# Volterra_Doughter_Board.net
KiCad netlist of a schematic drawn in EAGLE
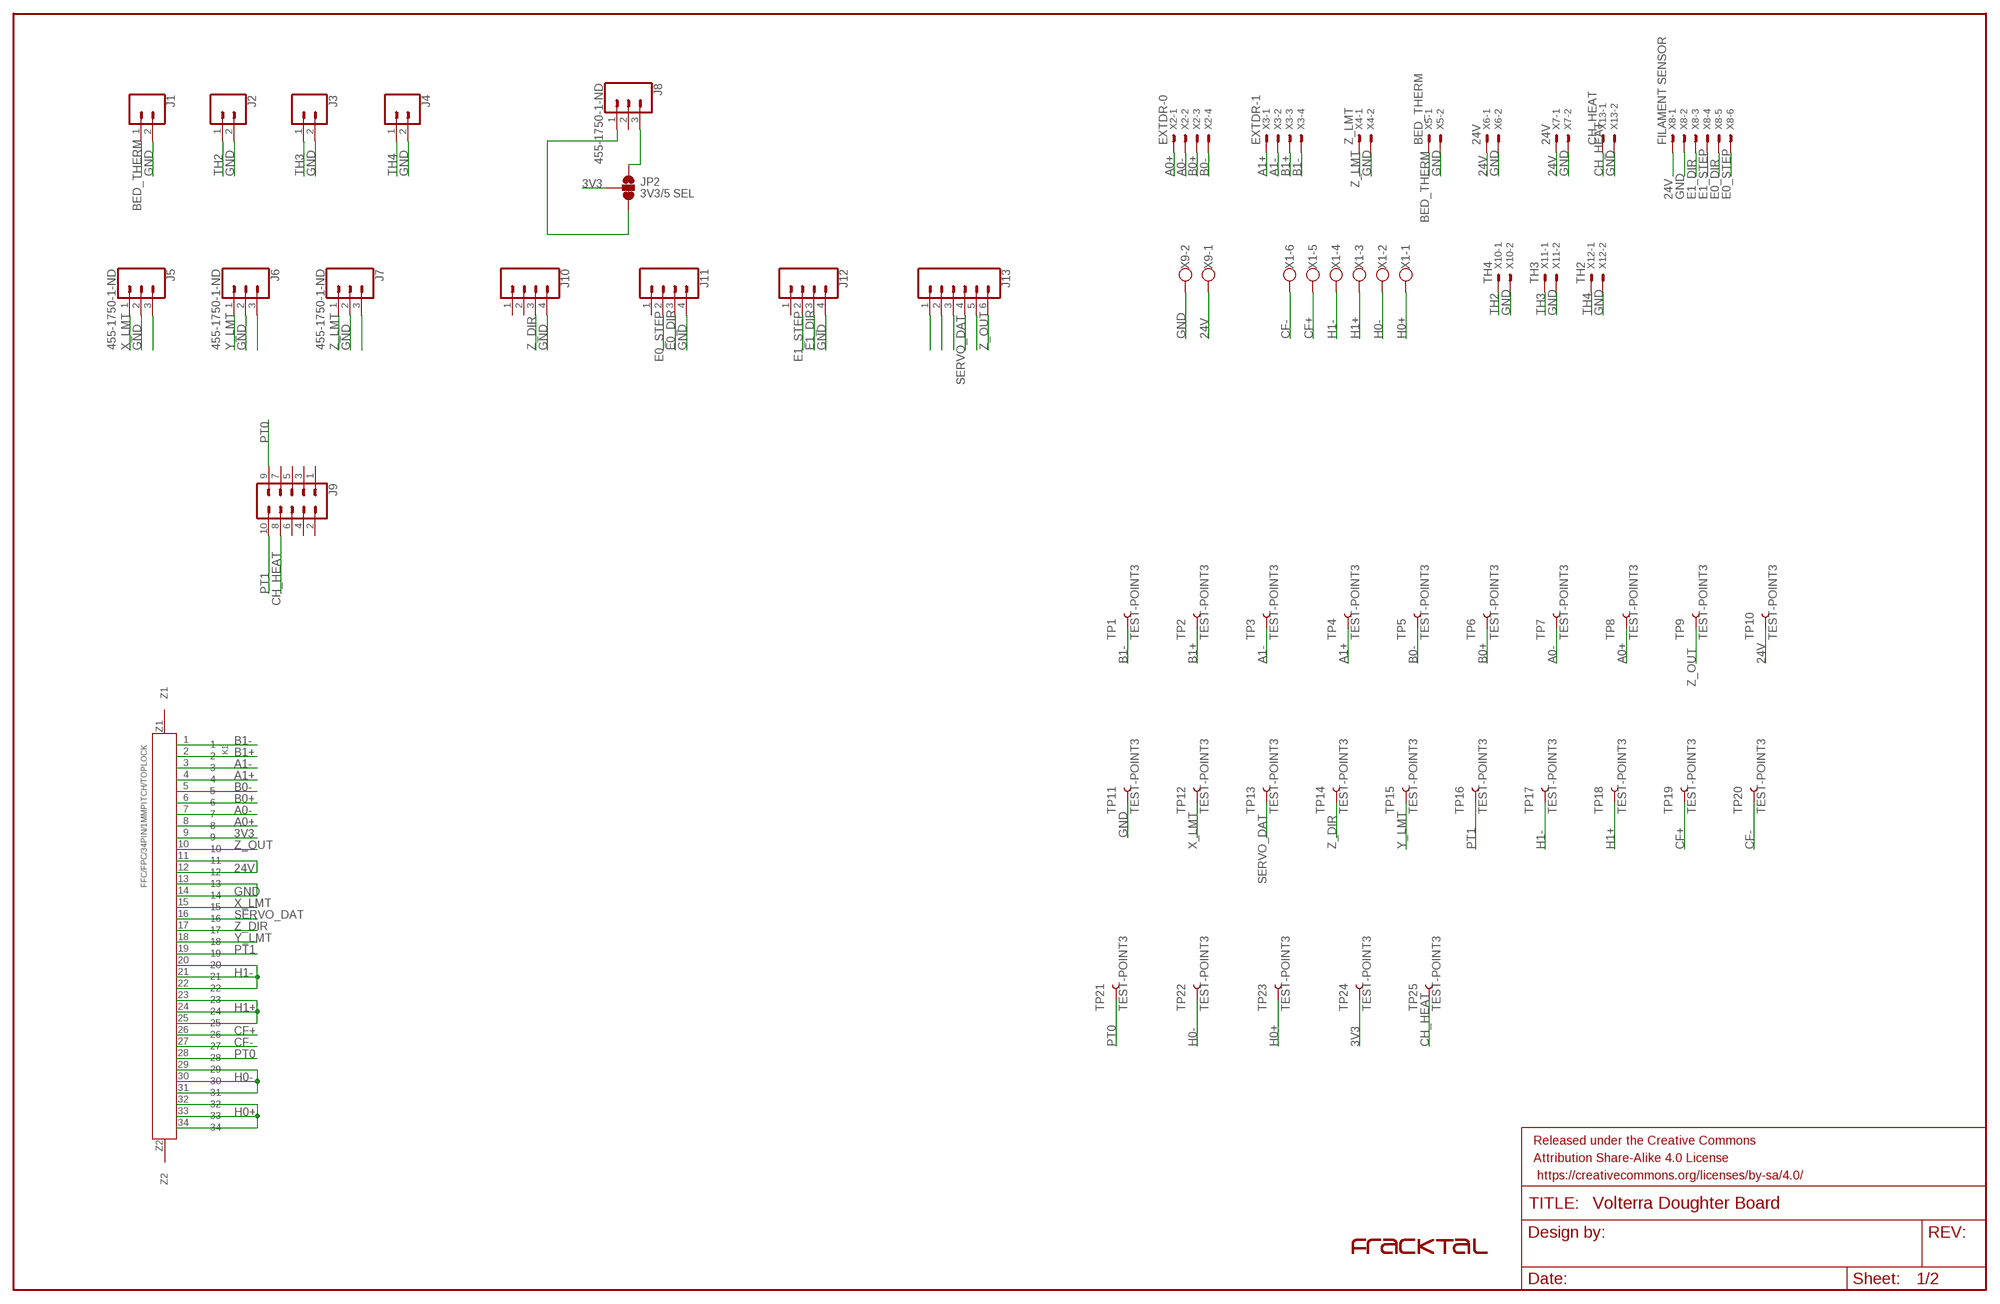
[diagram p0: schematic, sheet 1]

(export (version "E")
  (design (tool "Eeschema 10.0.6"))
  (components
    (comp (ref "FRAME1")
      (value "FRAME-LEDGER")
      (footprint "eagle-import:CREATIVE_COMMONS")
      (libsource (lib "eagle-import") (part "FRAME-LEDGER"))
    )
    (comp (ref "J1")
      (value "CONN_02")
      (footprint "eagle-import:1X02")
      (libsource (lib "eagle-import") (part "CONN_02"))
    )
    (comp (ref "J2")
      (value "CONN_02")
      (footprint "eagle-import:1X02")
      (libsource (lib "eagle-import") (part "CONN_02"))
    )
    (comp (ref "J3")
      (value "CONN_02")
      (footprint "eagle-import:1X02")
      (libsource (lib "eagle-import") (part "CONN_02"))
    )
    (comp (ref "J4")
      (value "CONN_02")
      (footprint "eagle-import:1X02")
      (libsource (lib "eagle-import") (part "CONN_02"))
    )
    (comp (ref "J5")
      (value "455-1750-1-ND")
      (footprint "eagle-import:1X03")
      (libsource (lib "eagle-import") (part "CONN_03"))
    )
    (comp (ref "J6")
      (value "455-1750-1-ND")
      (footprint "eagle-import:1X03")
      (libsource (lib "eagle-import") (part "CONN_03"))
    )
    (comp (ref "J7")
      (value "455-1750-1-ND")
      (footprint "eagle-import:1X03")
      (libsource (lib "eagle-import") (part "CONN_03"))
    )
    (comp (ref "J8")
      (value "455-1750-1-ND")
      (footprint "eagle-import:1X03")
      (libsource (lib "eagle-import") (part "CONN_03"))
    )
    (comp (ref "J9")
      (value "CONN_05X2PTH")
      (footprint "eagle-import:2X5")
      (libsource (lib "eagle-import") (part "CONN_05X2PTH"))
    )
    (comp (ref "J10")
      (value "CONN_04")
      (footprint "eagle-import:1X04")
      (libsource (lib "eagle-import") (part "CONN_04"))
    )
    (comp (ref "J11")
      (value "CONN_04")
      (footprint "eagle-import:1X04")
      (libsource (lib "eagle-import") (part "CONN_04"))
    )
    (comp (ref "J12")
      (value "CONN_04")
      (footprint "eagle-import:1X04")
      (libsource (lib "eagle-import") (part "CONN_04"))
    )
    (comp (ref "J13")
      (value "CONN_06SILK_FEMALE_PTH")
      (footprint "eagle-import:1X06")
      (libsource (lib "eagle-import") (part "CONN_06SILK_FEMALE_PTH"))
    )
    (comp (ref "JP2")
      (value "3V3/5 SEL")
      (footprint "eagle-import:SMT-JUMPER_3_1-NC_TRACE_SILK")
      (libsource (lib "eagle-import") (part "JUMPER-SMT_3_1-NC_TRACE_SILK"))
    )
    (comp (ref "K1")
      (value "FFC/FPC/34PIN/1MMPITCH/TOPLOCK")
      (footprint "eagle-import:34PIN_1MMPITCH_FFC_FPC")
      (libsource (lib "eagle-import") (part "FFC/FPC/34PIN/1MMPITCH/TOPLOCK"))
    )
    (comp (ref "TP1")
      (value "TEST-POINT3")
      (footprint "eagle-import:PAD.03X.03")
      (libsource (lib "eagle-import") (part "TEST-POINT3"))
    )
    (comp (ref "TP2")
      (value "TEST-POINT3")
      (footprint "eagle-import:PAD.03X.03")
      (libsource (lib "eagle-import") (part "TEST-POINT3"))
    )
    (comp (ref "TP3")
      (value "TEST-POINT3")
      (footprint "eagle-import:PAD.03X.03")
      (libsource (lib "eagle-import") (part "TEST-POINT3"))
    )
    (comp (ref "TP4")
      (value "TEST-POINT3")
      (footprint "eagle-import:PAD.03X.03")
      (libsource (lib "eagle-import") (part "TEST-POINT3"))
    )
    (comp (ref "TP5")
      (value "TEST-POINT3")
      (footprint "eagle-import:PAD.03X.03")
      (libsource (lib "eagle-import") (part "TEST-POINT3"))
    )
    (comp (ref "TP6")
      (value "TEST-POINT3")
      (footprint "eagle-import:PAD.03X.03")
      (libsource (lib "eagle-import") (part "TEST-POINT3"))
    )
    (comp (ref "TP7")
      (value "TEST-POINT3")
      (footprint "eagle-import:PAD.03X.03")
      (libsource (lib "eagle-import") (part "TEST-POINT3"))
    )
    (comp (ref "TP8")
      (value "TEST-POINT3")
      (footprint "eagle-import:PAD.03X.03")
      (libsource (lib "eagle-import") (part "TEST-POINT3"))
    )
    (comp (ref "TP9")
      (value "TEST-POINT3")
      (footprint "eagle-import:PAD.03X.03")
      (libsource (lib "eagle-import") (part "TEST-POINT3"))
    )
    (comp (ref "TP10")
      (value "TEST-POINT3")
      (footprint "eagle-import:PAD.03X.03")
      (libsource (lib "eagle-import") (part "TEST-POINT3"))
    )
    (comp (ref "TP11")
      (value "TEST-POINT3")
      (footprint "eagle-import:PAD.03X.03")
      (libsource (lib "eagle-import") (part "TEST-POINT3"))
    )
    (comp (ref "TP12")
      (value "TEST-POINT3")
      (footprint "eagle-import:PAD.03X.03")
      (libsource (lib "eagle-import") (part "TEST-POINT3"))
    )
    (comp (ref "TP13")
      (value "TEST-POINT3")
      (footprint "eagle-import:PAD.03X.03")
      (libsource (lib "eagle-import") (part "TEST-POINT3"))
    )
    (comp (ref "TP14")
      (value "TEST-POINT3")
      (footprint "eagle-import:PAD.03X.03")
      (libsource (lib "eagle-import") (part "TEST-POINT3"))
    )
    (comp (ref "TP15")
      (value "TEST-POINT3")
      (footprint "eagle-import:PAD.03X.03")
      (libsource (lib "eagle-import") (part "TEST-POINT3"))
    )
    (comp (ref "TP16")
      (value "TEST-POINT3")
      (footprint "eagle-import:PAD.03X.03")
      (libsource (lib "eagle-import") (part "TEST-POINT3"))
    )
    (comp (ref "TP17")
      (value "TEST-POINT3")
      (footprint "eagle-import:PAD.03X.03")
      (libsource (lib "eagle-import") (part "TEST-POINT3"))
    )
    (comp (ref "TP18")
      (value "TEST-POINT3")
      (footprint "eagle-import:PAD.03X.03")
      (libsource (lib "eagle-import") (part "TEST-POINT3"))
    )
    (comp (ref "TP19")
      (value "TEST-POINT3")
      (footprint "eagle-import:PAD.03X.03")
      (libsource (lib "eagle-import") (part "TEST-POINT3"))
    )
    (comp (ref "TP20")
      (value "TEST-POINT3")
      (footprint "eagle-import:PAD.03X.03")
      (libsource (lib "eagle-import") (part "TEST-POINT3"))
    )
    (comp (ref "TP21")
      (value "TEST-POINT3")
      (footprint "eagle-import:PAD.03X.03")
      (libsource (lib "eagle-import") (part "TEST-POINT3"))
    )
    (comp (ref "TP22")
      (value "TEST-POINT3")
      (footprint "eagle-import:PAD.03X.03")
      (libsource (lib "eagle-import") (part "TEST-POINT3"))
    )
    (comp (ref "TP23")
      (value "TEST-POINT3")
      (footprint "eagle-import:PAD.03X.03")
      (libsource (lib "eagle-import") (part "TEST-POINT3"))
    )
    (comp (ref "TP24")
      (value "TEST-POINT3")
      (footprint "eagle-import:PAD.03X.03")
      (libsource (lib "eagle-import") (part "TEST-POINT3"))
    )
    (comp (ref "TP25")
      (value "TEST-POINT3")
      (footprint "eagle-import:PAD.03X.03")
      (libsource (lib "eagle-import") (part "TEST-POINT3"))
    )
    (comp (ref "U$1")
      (value "FRACKTALLOGO")
      (footprint "eagle-import:FRACKTALLOGO")
      (libsource (lib "eagle-import") (part "FRACKTALLOGO"))
    )
    (comp (ref "X1")
      (value "W237-6")
      (footprint "eagle-import:W237-6")
      (libsource (lib "eagle-import") (part "W237-6"))
    )
    (comp (ref "X2")
      (value "EXTDR-0")
      (footprint "eagle-import:JST-XH-04-PACKAGE-LONG-PAD")
      (libsource (lib "eagle-import") (part "JST-XH-04-PIN-LONG-PAD"))
    )
    (comp (ref "X3")
      (value "EXTDR-1")
      (footprint "eagle-import:JST-XH-04-PACKAGE-LONG-PAD")
      (libsource (lib "eagle-import") (part "JST-XH-04-PIN-LONG-PAD"))
    )
    (comp (ref "X4")
      (value "Z_LMT")
      (footprint "eagle-import:JST-XH-02-PACKAGE-LONG-PAD")
      (libsource (lib "eagle-import") (part "JST-XH-02-PIN-LONG-PAD"))
    )
    (comp (ref "X5")
      (value "BED_THERM")
      (footprint "eagle-import:JST-XH-02-PACKAGE-LONG-PAD")
      (libsource (lib "eagle-import") (part "JST-XH-02-PIN-LONG-PAD"))
    )
    (comp (ref "X6")
      (value "24V")
      (footprint "eagle-import:JST-XH-02-PACKAGE-LONG-PAD")
      (libsource (lib "eagle-import") (part "JST-XH-02-PIN-LONG-PAD"))
    )
    (comp (ref "X7")
      (value "24V")
      (footprint "eagle-import:JST-XH-02-PACKAGE-LONG-PAD")
      (libsource (lib "eagle-import") (part "JST-XH-02-PIN-LONG-PAD"))
    )
    (comp (ref "X8")
      (value "FILAMENT SENSOR")
      (footprint "eagle-import:JST-XH-06-PACKAGE-LONG-PAD")
      (libsource (lib "eagle-import") (part "JST-XH-06-PIN-LONG-PAD"))
    )
    (comp (ref "X9")
      (value "W237-102")
      (footprint "eagle-import:W237-102")
      (fields (field (name "MPN") "237-102"))
      (libsource (lib "eagle-import") (part "W237-102"))
    )
    (comp (ref "X10")
      (value "TH4")
      (footprint "eagle-import:JST-XH-02-PACKAGE-LONG-PAD")
      (libsource (lib "eagle-import") (part "JST-XH-02-PIN-LONG-PAD"))
    )
    (comp (ref "X11")
      (value "TH3")
      (footprint "eagle-import:JST-XH-02-PACKAGE-LONG-PAD")
      (libsource (lib "eagle-import") (part "JST-XH-02-PIN-LONG-PAD"))
    )
    (comp (ref "X12")
      (value "TH2")
      (footprint "eagle-import:JST-XH-02-PACKAGE-LONG-PAD")
      (libsource (lib "eagle-import") (part "JST-XH-02-PIN-LONG-PAD"))
    )
    (comp (ref "X13")
      (value "CH_HEAT")
      (footprint "eagle-import:JST-XH-02-PACKAGE-LONG-PAD")
      (libsource (lib "eagle-import") (part "JST-XH-02-PIN-LONG-PAD"))
    )
  )
  (nets
    (net (code "1") (name "3V3") (class "Default")
      (node (ref "JP2") (pin "2") (pinfunction "2_2") (pintype "passive"))
      (node (ref "K1") (pin "9") (pinfunction "9_9") (pintype "bidirectional"))
      (node (ref "TP24") (pin "P$1") (pinfunction "1_P$1") (pintype "bidirectional"))
    )
    (net (code "2") (name "24V") (class "Default")
      (node (ref "K1") (pin "11") (pinfunction "11_11") (pintype "bidirectional"))
      (node (ref "K1") (pin "12") (pinfunction "12_12") (pintype "bidirectional"))
      (node (ref "TP10") (pin "P$1") (pinfunction "1_P$1") (pintype "bidirectional"))
      (node (ref "X6") (pin "1") (pinfunction "S_1") (pintype "passive"))
      (node (ref "X7") (pin "1") (pinfunction "S_1") (pintype "passive"))
      (node (ref "X8") (pin "1") (pinfunction "S_1") (pintype "passive"))
      (node (ref "X9") (pin "1") (pinfunction "KL_1") (pintype "passive"))
    )
    (net (code "3") (name "A0+") (class "Default")
      (node (ref "K1") (pin "8") (pinfunction "8_8") (pintype "bidirectional"))
      (node (ref "TP8") (pin "P$1") (pinfunction "1_P$1") (pintype "bidirectional"))
      (node (ref "X2") (pin "1") (pinfunction "S_1") (pintype "passive"))
    )
    (net (code "4") (name "A0-") (class "Default")
      (node (ref "K1") (pin "7") (pinfunction "7_7") (pintype "bidirectional"))
      (node (ref "TP7") (pin "P$1") (pinfunction "1_P$1") (pintype "bidirectional"))
      (node (ref "X2") (pin "2") (pinfunction "S_2") (pintype "passive"))
    )
    (net (code "5") (name "A1+") (class "Default")
      (node (ref "K1") (pin "4") (pinfunction "4_4") (pintype "bidirectional"))
      (node (ref "TP4") (pin "P$1") (pinfunction "1_P$1") (pintype "bidirectional"))
      (node (ref "X3") (pin "1") (pinfunction "S_1") (pintype "passive"))
    )
    (net (code "6") (name "A1-") (class "Default")
      (node (ref "K1") (pin "3") (pinfunction "3_3") (pintype "bidirectional"))
      (node (ref "TP3") (pin "P$1") (pinfunction "1_P$1") (pintype "bidirectional"))
      (node (ref "X3") (pin "2") (pinfunction "S_2") (pintype "passive"))
    )
    (net (code "7") (name "B0+") (class "Default")
      (node (ref "K1") (pin "6") (pinfunction "6_6") (pintype "bidirectional"))
      (node (ref "TP6") (pin "P$1") (pinfunction "1_P$1") (pintype "bidirectional"))
      (node (ref "X2") (pin "3") (pinfunction "S_3") (pintype "passive"))
    )
    (net (code "8") (name "B0-") (class "Default")
      (node (ref "K1") (pin "5") (pinfunction "5_5") (pintype "bidirectional"))
      (node (ref "TP5") (pin "P$1") (pinfunction "1_P$1") (pintype "bidirectional"))
      (node (ref "X2") (pin "4") (pinfunction "S_4") (pintype "passive"))
    )
    (net (code "9") (name "B1+") (class "Default")
      (node (ref "K1") (pin "2") (pinfunction "2_2") (pintype "bidirectional"))
      (node (ref "TP2") (pin "P$1") (pinfunction "1_P$1") (pintype "bidirectional"))
      (node (ref "X3") (pin "3") (pinfunction "S_3") (pintype "passive"))
    )
    (net (code "10") (name "B1-") (class "Default")
      (node (ref "K1") (pin "1") (pinfunction "1_1") (pintype "bidirectional"))
      (node (ref "TP1") (pin "P$1") (pinfunction "1_P$1") (pintype "bidirectional"))
      (node (ref "X3") (pin "4") (pinfunction "S_4") (pintype "passive"))
    )
    (net (code "11") (name "BED_THERM") (class "Default")
      (node (ref "J1") (pin "1") (pinfunction "1_1") (pintype "passive"))
      (node (ref "X5") (pin "1") (pinfunction "S_1") (pintype "passive"))
    )
    (net (code "12") (name "CF+") (class "Default")
      (node (ref "K1") (pin "26") (pinfunction "26_26") (pintype "bidirectional"))
      (node (ref "TP19") (pin "P$1") (pinfunction "1_P$1") (pintype "bidirectional"))
      (node (ref "X1") (pin "5") (pinfunction "KL_5") (pintype "passive"))
    )
    (net (code "13") (name "CF-") (class "Default")
      (node (ref "K1") (pin "27") (pinfunction "27_27") (pintype "bidirectional"))
      (node (ref "TP20") (pin "P$1") (pinfunction "1_P$1") (pintype "bidirectional"))
      (node (ref "X1") (pin "6") (pinfunction "KL_6") (pintype "passive"))
    )
    (net (code "14") (name "CH_HEAT") (class "Default")
      (node (ref "J9") (pin "8") (pinfunction "8_8") (pintype "passive"))
      (node (ref "TP25") (pin "P$1") (pinfunction "1_P$1") (pintype "bidirectional"))
      (node (ref "X13") (pin "1") (pinfunction "S_1") (pintype "passive"))
    )
    (net (code "15") (name "E0_DIR") (class "Default")
      (node (ref "J11") (pin "3") (pinfunction "3_3") (pintype "passive"))
      (node (ref "X8") (pin "5") (pinfunction "S_5") (pintype "passive"))
    )
    (net (code "16") (name "E0_STEP") (class "Default")
      (node (ref "J11") (pin "2") (pinfunction "2_2") (pintype "passive"))
      (node (ref "X8") (pin "6") (pinfunction "S_6") (pintype "passive"))
    )
    (net (code "17") (name "E1_DIR") (class "Default")
      (node (ref "J12") (pin "3") (pinfunction "3_3") (pintype "passive"))
      (node (ref "X8") (pin "3") (pinfunction "S_3") (pintype "passive"))
    )
    (net (code "18") (name "E1_STEP") (class "Default")
      (node (ref "J12") (pin "2") (pinfunction "2_2") (pintype "passive"))
      (node (ref "X8") (pin "4") (pinfunction "S_4") (pintype "passive"))
    )
    (net (code "19") (name "GND") (class "Default")
      (node (ref "J1") (pin "2") (pinfunction "2_2") (pintype "passive"))
      (node (ref "J10") (pin "4") (pinfunction "4_4") (pintype "passive"))
      (node (ref "J11") (pin "4") (pinfunction "4_4") (pintype "passive"))
      (node (ref "J12") (pin "4") (pinfunction "4_4") (pintype "passive"))
      (node (ref "J2") (pin "2") (pinfunction "2_2") (pintype "passive"))
      (node (ref "J3") (pin "2") (pinfunction "2_2") (pintype "passive"))
      (node (ref "J4") (pin "2") (pinfunction "2_2") (pintype "passive"))
      (node (ref "J5") (pin "2") (pinfunction "2_2") (pintype "passive"))
      (node (ref "J6") (pin "2") (pinfunction "2_2") (pintype "passive"))
      (node (ref "J7") (pin "2") (pinfunction "2_2") (pintype "passive"))
      (node (ref "K1") (pin "13") (pinfunction "13_13") (pintype "bidirectional"))
      (node (ref "K1") (pin "14") (pinfunction "14_14") (pintype "bidirectional"))
      (node (ref "TP11") (pin "P$1") (pinfunction "1_P$1") (pintype "bidirectional"))
      (node (ref "X10") (pin "2") (pinfunction "S_2") (pintype "passive"))
      (node (ref "X11") (pin "2") (pinfunction "S_2") (pintype "passive"))
      (node (ref "X12") (pin "2") (pinfunction "S_2") (pintype "passive"))
      (node (ref "X13") (pin "2") (pinfunction "S_2") (pintype "passive"))
      (node (ref "X4") (pin "2") (pinfunction "S_2") (pintype "passive"))
      (node (ref "X5") (pin "2") (pinfunction "S_2") (pintype "passive"))
      (node (ref "X6") (pin "2") (pinfunction "S_2") (pintype "passive"))
      (node (ref "X7") (pin "2") (pinfunction "S_2") (pintype "passive"))
      (node (ref "X8") (pin "2") (pinfunction "S_2") (pintype "passive"))
      (node (ref "X9") (pin "2") (pinfunction "KL_2") (pintype "passive"))
    )
    (net (code "20") (name "H0+") (class "Default")
      (node (ref "K1") (pin "32") (pinfunction "32_32") (pintype "bidirectional"))
      (node (ref "K1") (pin "33") (pinfunction "33_33") (pintype "bidirectional"))
      (node (ref "K1") (pin "34") (pinfunction "34_34") (pintype "bidirectional"))
      (node (ref "TP23") (pin "P$1") (pinfunction "1_P$1") (pintype "bidirectional"))
      (node (ref "X1") (pin "1") (pinfunction "KL_1") (pintype "passive"))
    )
    (net (code "21") (name "H0-") (class "Default")
      (node (ref "K1") (pin "29") (pinfunction "29_29") (pintype "bidirectional"))
      (node (ref "K1") (pin "30") (pinfunction "30_30") (pintype "bidirectional"))
      (node (ref "K1") (pin "31") (pinfunction "31_31") (pintype "bidirectional"))
      (node (ref "TP22") (pin "P$1") (pinfunction "1_P$1") (pintype "bidirectional"))
      (node (ref "X1") (pin "2") (pinfunction "KL_2") (pintype "passive"))
    )
    (net (code "22") (name "H1+") (class "Default")
      (node (ref "K1") (pin "23") (pinfunction "23_23") (pintype "bidirectional"))
      (node (ref "K1") (pin "24") (pinfunction "24_24") (pintype "bidirectional"))
      (node (ref "K1") (pin "25") (pinfunction "25_25") (pintype "bidirectional"))
      (node (ref "TP18") (pin "P$1") (pinfunction "1_P$1") (pintype "bidirectional"))
      (node (ref "X1") (pin "3") (pinfunction "KL_3") (pintype "passive"))
    )
    (net (code "23") (name "H1-") (class "Default")
      (node (ref "K1") (pin "20") (pinfunction "20_20") (pintype "bidirectional"))
      (node (ref "K1") (pin "21") (pinfunction "21_21") (pintype "bidirectional"))
      (node (ref "K1") (pin "22") (pinfunction "22_22") (pintype "bidirectional"))
      (node (ref "TP17") (pin "P$1") (pinfunction "1_P$1") (pintype "bidirectional"))
      (node (ref "X1") (pin "4") (pinfunction "KL_4") (pintype "passive"))
    )
    (net (code "24") (name "Net-(J8-Pad1)") (class "Default")
      (node (ref "J8") (pin "1") (pinfunction "1_1") (pintype "passive"))
      (node (ref "JP2") (pin "3") (pinfunction "3_3") (pintype "passive"))
    )
    (net (code "25") (name "Net-(J8-Pad3)") (class "Default")
      (node (ref "J8") (pin "3") (pinfunction "3_3") (pintype "passive"))
      (node (ref "JP2") (pin "1") (pinfunction "1_1") (pintype "passive"))
    )
    (net (code "26") (name "PT0") (class "Default")
      (node (ref "J9") (pin "9") (pinfunction "9_9") (pintype "passive"))
      (node (ref "K1") (pin "28") (pinfunction "28_28") (pintype "bidirectional"))
      (node (ref "TP21") (pin "P$1") (pinfunction "1_P$1") (pintype "bidirectional"))
    )
    (net (code "27") (name "PT1") (class "Default")
      (node (ref "J9") (pin "10") (pinfunction "10_10") (pintype "passive"))
      (node (ref "K1") (pin "19") (pinfunction "19_19") (pintype "bidirectional"))
      (node (ref "TP16") (pin "P$1") (pinfunction "1_P$1") (pintype "bidirectional"))
    )
    (net (code "28") (name "SERVO_DAT") (class "Default")
      (node (ref "J13") (pin "4") (pinfunction "4_4") (pintype "passive"))
      (node (ref "K1") (pin "16") (pinfunction "16_16") (pintype "bidirectional"))
      (node (ref "TP13") (pin "P$1") (pinfunction "1_P$1") (pintype "bidirectional"))
    )
    (net (code "29") (name "TH2") (class "Default")
      (node (ref "J2") (pin "1") (pinfunction "1_1") (pintype "passive"))
      (node (ref "X10") (pin "1") (pinfunction "S_1") (pintype "passive"))
    )
    (net (code "30") (name "TH3") (class "Default")
      (node (ref "J3") (pin "1") (pinfunction "1_1") (pintype "passive"))
      (node (ref "X11") (pin "1") (pinfunction "S_1") (pintype "passive"))
    )
    (net (code "31") (name "TH4") (class "Default")
      (node (ref "J4") (pin "1") (pinfunction "1_1") (pintype "passive"))
      (node (ref "X12") (pin "1") (pinfunction "S_1") (pintype "passive"))
    )
    (net (code "32") (name "X_LMT") (class "Default")
      (node (ref "J5") (pin "1") (pinfunction "1_1") (pintype "passive"))
      (node (ref "K1") (pin "15") (pinfunction "15_15") (pintype "bidirectional"))
      (node (ref "TP12") (pin "P$1") (pinfunction "1_P$1") (pintype "bidirectional"))
    )
    (net (code "33") (name "Y_LMT") (class "Default")
      (node (ref "J6") (pin "1") (pinfunction "1_1") (pintype "passive"))
      (node (ref "K1") (pin "18") (pinfunction "18_18") (pintype "bidirectional"))
      (node (ref "TP15") (pin "P$1") (pinfunction "1_P$1") (pintype "bidirectional"))
    )
    (net (code "34") (name "Z_DIR") (class "Default")
      (node (ref "J10") (pin "3") (pinfunction "3_3") (pintype "passive"))
      (node (ref "K1") (pin "17") (pinfunction "17_17") (pintype "bidirectional"))
      (node (ref "TP14") (pin "P$1") (pinfunction "1_P$1") (pintype "bidirectional"))
    )
    (net (code "35") (name "Z_LMT") (class "Default")
      (node (ref "J7") (pin "1") (pinfunction "1_1") (pintype "passive"))
      (node (ref "X4") (pin "1") (pinfunction "S_1") (pintype "passive"))
    )
    (net (code "36") (name "Z_OUT") (class "Default")
      (node (ref "J13") (pin "6") (pinfunction "6_6") (pintype "passive"))
      (node (ref "K1") (pin "10") (pinfunction "10_10") (pintype "bidirectional"))
      (node (ref "TP9") (pin "P$1") (pinfunction "1_P$1") (pintype "bidirectional"))
    )
    (net (code "37") (name "unconnected-(J5-Pad3)") (class "Default")
      (node (ref "J5") (pin "3") (pinfunction "3_3") (pintype "passive"))
    )
    (net (code "38") (name "unconnected-(J6-Pad3)") (class "Default")
      (node (ref "J6") (pin "3") (pinfunction "3_3") (pintype "passive"))
    )
    (net (code "39") (name "unconnected-(J7-Pad3)") (class "Default")
      (node (ref "J7") (pin "3") (pinfunction "3_3") (pintype "passive"))
    )
    (net (code "40") (name "unconnected-(J8-Pad2)") (class "Default")
      (node (ref "J8") (pin "2") (pinfunction "2_2") (pintype "passive"))
    )
    (net (code "41") (name "unconnected-(J9-Pad1)") (class "Default")
      (node (ref "J9") (pin "1") (pinfunction "1_1") (pintype "passive"))
    )
    (net (code "42") (name "unconnected-(J9-Pad2)") (class "Default")
      (node (ref "J9") (pin "2") (pinfunction "2_2") (pintype "passive"))
    )
    (net (code "43") (name "unconnected-(J9-Pad3)") (class "Default")
      (node (ref "J9") (pin "3") (pinfunction "3_3") (pintype "passive"))
    )
    (net (code "44") (name "unconnected-(J9-Pad4)") (class "Default")
      (node (ref "J9") (pin "4") (pinfunction "4_4") (pintype "passive"))
    )
    (net (code "45") (name "unconnected-(J9-Pad5)") (class "Default")
      (node (ref "J9") (pin "5") (pinfunction "5_5") (pintype "passive"))
    )
    (net (code "46") (name "unconnected-(J9-Pad6)") (class "Default")
      (node (ref "J9") (pin "6") (pinfunction "6_6") (pintype "passive"))
    )
    (net (code "47") (name "unconnected-(J9-Pad7)") (class "Default")
      (node (ref "J9") (pin "7") (pinfunction "7_7") (pintype "passive"))
    )
    (net (code "48") (name "unconnected-(J10-Pad1)") (class "Default")
      (node (ref "J10") (pin "1") (pinfunction "1_1") (pintype "passive"))
    )
    (net (code "49") (name "unconnected-(J10-Pad2)") (class "Default")
      (node (ref "J10") (pin "2") (pinfunction "2_2") (pintype "passive"))
    )
    (net (code "50") (name "unconnected-(J11-Pad1)") (class "Default")
      (node (ref "J11") (pin "1") (pinfunction "1_1") (pintype "passive"))
    )
    (net (code "51") (name "unconnected-(J12-Pad1)") (class "Default")
      (node (ref "J12") (pin "1") (pinfunction "1_1") (pintype "passive"))
    )
    (net (code "52") (name "unconnected-(J13-Pad1)") (class "Default")
      (node (ref "J13") (pin "1") (pinfunction "1_1") (pintype "passive"))
    )
    (net (code "53") (name "unconnected-(J13-Pad2)") (class "Default")
      (node (ref "J13") (pin "2") (pinfunction "2_2") (pintype "passive"))
    )
    (net (code "54") (name "unconnected-(J13-Pad3)") (class "Default")
      (node (ref "J13") (pin "3") (pinfunction "3_3") (pintype "passive"))
    )
    (net (code "55") (name "unconnected-(J13-Pad5)") (class "Default")
      (node (ref "J13") (pin "5") (pinfunction "5_5") (pintype "passive"))
    )
    (net (code "56") (name "unconnected-(K1-PadZ1)") (class "Default")
      (node (ref "K1") (pin "Z1") (pinfunction "Z1_Z1") (pintype "bidirectional"))
    )
    (net (code "57") (name "unconnected-(K1-PadZ2)") (class "Default")
      (node (ref "K1") (pin "Z2") (pinfunction "Z2_Z2") (pintype "bidirectional"))
    )
  )
)
